# RGB_FPGA_CSI.net
KiCad netlist of a schematic drawn in Altium Designer
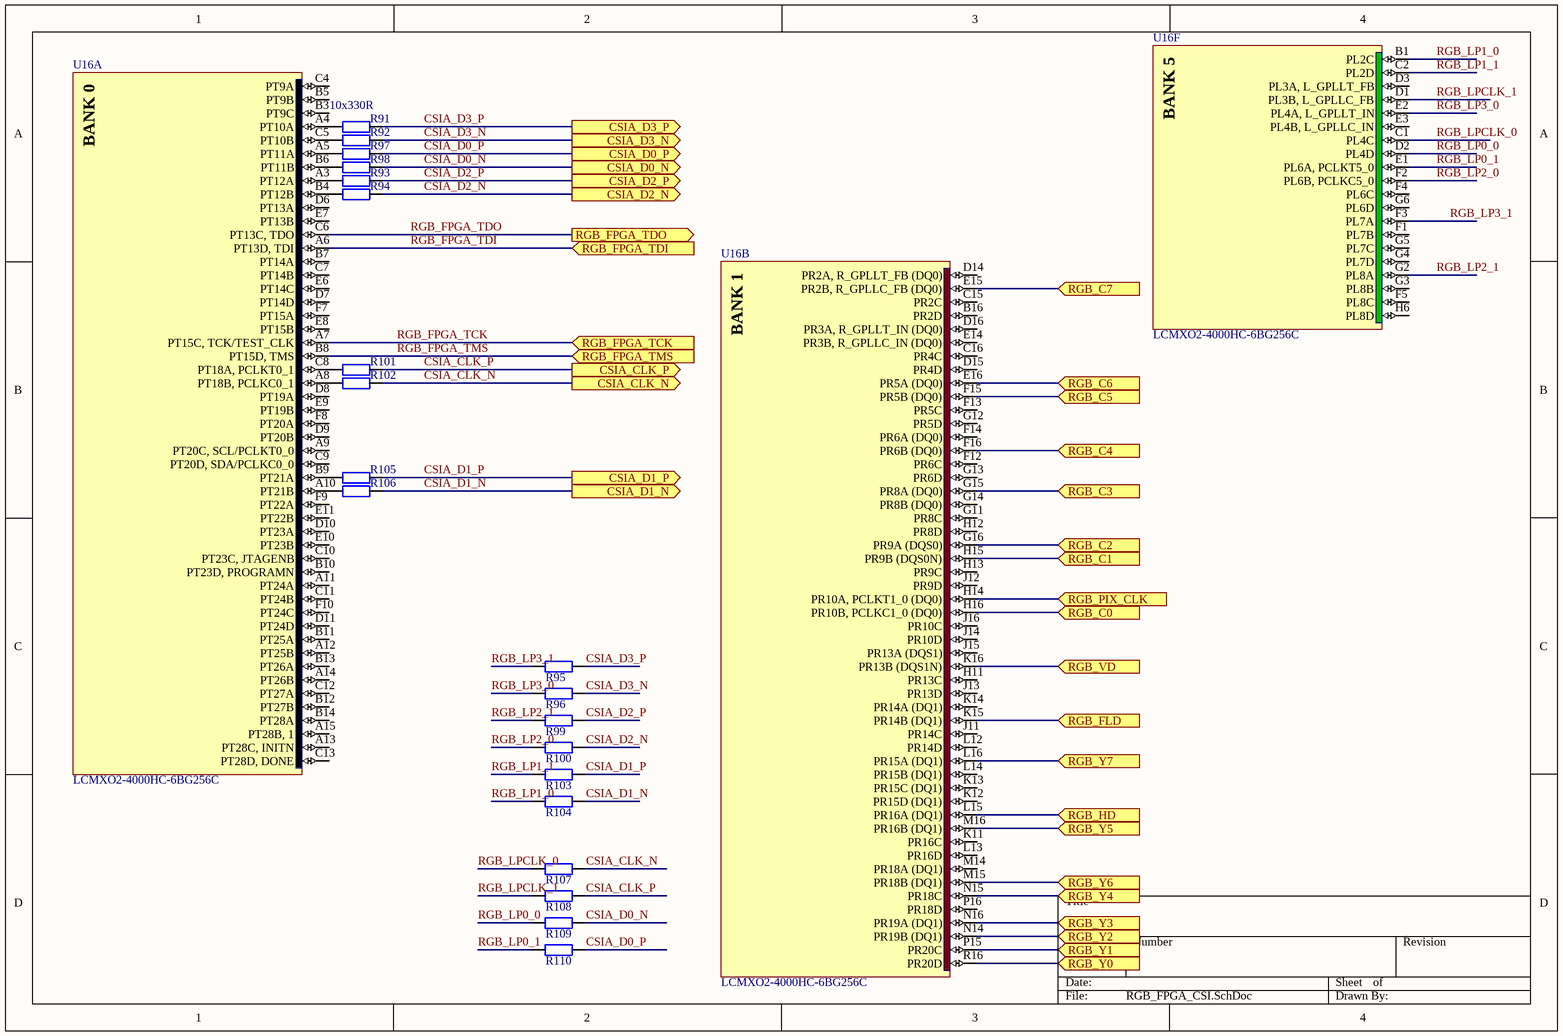
[diagram p0: RGB_FPGA_CSI.SchDoc]

(export (version "E")
  (design (tool "Eeschema 10.0.6"))
  (components
    (comp (ref "R91")
      (value "CRCW0402330RFKED")
      (footprint "0402R_M")
      (description "RES SMD 330 OHM 1% 1/16W 0402")
      (fields (field (name "MANUFACTURER") "Vishay Dale") (field (name "TOLERANCE") "±1%"))
      (libsource (lib "KMTI-main") (part "CRCW0402330RFKED"))
    )
    (comp (ref "R92")
      (value "CRCW0402330RFKED")
      (footprint "0402R_M")
      (description "RES SMD 330 OHM 1% 1/16W 0402")
      (fields (field (name "MANUFACTURER") "Vishay Dale") (field (name "TOLERANCE") "±1%"))
      (libsource (lib "KMTI-main") (part "CRCW0402330RFKED"))
    )
    (comp (ref "R93")
      (value "CRCW0402330RFKED")
      (footprint "0402R_M")
      (description "RES SMD 330 OHM 1% 1/16W 0402")
      (fields (field (name "MANUFACTURER") "Vishay Dale") (field (name "TOLERANCE") "±1%"))
      (libsource (lib "KMTI-main") (part "CRCW0402330RFKED"))
    )
    (comp (ref "R94")
      (value "CRCW0402330RFKED")
      (footprint "0402R_M")
      (description "RES SMD 330 OHM 1% 1/16W 0402")
      (fields (field (name "MANUFACTURER") "Vishay Dale") (field (name "TOLERANCE") "±1%"))
      (libsource (lib "KMTI-main") (part "CRCW0402330RFKED"))
    )
    (comp (ref "R95")
      (value "CRCW040249R9FKED")
      (footprint "0402R_M")
      (description "RES SMD 49.9 OHM 1% 1/16W 0402")
      (fields (field (name "MANUFACTURER") "Vishay Dale") (field (name "TOLERANCE") "±1%"))
      (libsource (lib "KMTI-main") (part "CRCW040249R9FKED"))
    )
    (comp (ref "R96")
      (value "CRCW040249R9FKED")
      (footprint "0402R_M")
      (description "RES SMD 49.9 OHM 1% 1/16W 0402")
      (fields (field (name "MANUFACTURER") "Vishay Dale") (field (name "TOLERANCE") "±1%"))
      (libsource (lib "KMTI-main") (part "CRCW040249R9FKED"))
    )
    (comp (ref "R97")
      (value "CRCW0402330RFKED")
      (footprint "0402R_M")
      (description "RES SMD 330 OHM 1% 1/16W 0402")
      (fields (field (name "MANUFACTURER") "Vishay Dale") (field (name "TOLERANCE") "±1%"))
      (libsource (lib "KMTI-main") (part "CRCW0402330RFKED"))
    )
    (comp (ref "R98")
      (value "CRCW0402330RFKED")
      (footprint "0402R_M")
      (description "RES SMD 330 OHM 1% 1/16W 0402")
      (fields (field (name "MANUFACTURER") "Vishay Dale") (field (name "TOLERANCE") "±1%"))
      (libsource (lib "KMTI-main") (part "CRCW0402330RFKED"))
    )
    (comp (ref "R99")
      (value "CRCW040249R9FKED")
      (footprint "0402R_M")
      (description "RES SMD 49.9 OHM 1% 1/16W 0402")
      (fields (field (name "MANUFACTURER") "Vishay Dale") (field (name "TOLERANCE") "±1%"))
      (libsource (lib "KMTI-main") (part "CRCW040249R9FKED"))
    )
    (comp (ref "R100")
      (value "CRCW040249R9FKED")
      (footprint "0402R_M")
      (description "RES SMD 49.9 OHM 1% 1/16W 0402")
      (fields (field (name "MANUFACTURER") "Vishay Dale") (field (name "TOLERANCE") "±1%"))
      (libsource (lib "KMTI-main") (part "CRCW040249R9FKED"))
    )
    (comp (ref "R101")
      (value "CRCW0402330RFKED")
      (footprint "0402R_M")
      (description "RES SMD 330 OHM 1% 1/16W 0402")
      (fields (field (name "MANUFACTURER") "Vishay Dale") (field (name "TOLERANCE") "±1%"))
      (libsource (lib "KMTI-main") (part "CRCW0402330RFKED"))
    )
    (comp (ref "R102")
      (value "CRCW0402330RFKED")
      (footprint "0402R_M")
      (description "RES SMD 330 OHM 1% 1/16W 0402")
      (fields (field (name "MANUFACTURER") "Vishay Dale") (field (name "TOLERANCE") "±1%"))
      (libsource (lib "KMTI-main") (part "CRCW0402330RFKED"))
    )
    (comp (ref "R103")
      (value "CRCW040249R9FKED")
      (footprint "0402R_M")
      (description "RES SMD 49.9 OHM 1% 1/16W 0402")
      (fields (field (name "MANUFACTURER") "Vishay Dale") (field (name "TOLERANCE") "±1%"))
      (libsource (lib "KMTI-main") (part "CRCW040249R9FKED"))
    )
    (comp (ref "R104")
      (value "CRCW040249R9FKED")
      (footprint "0402R_M")
      (description "RES SMD 49.9 OHM 1% 1/16W 0402")
      (fields (field (name "MANUFACTURER") "Vishay Dale") (field (name "TOLERANCE") "±1%"))
      (libsource (lib "KMTI-main") (part "CRCW040249R9FKED"))
    )
    (comp (ref "R105")
      (value "CRCW0402330RFKED")
      (footprint "0402R_M")
      (description "RES SMD 330 OHM 1% 1/16W 0402")
      (fields (field (name "MANUFACTURER") "Vishay Dale") (field (name "TOLERANCE") "±1%"))
      (libsource (lib "KMTI-main") (part "CRCW0402330RFKED"))
    )
    (comp (ref "R106")
      (value "CRCW0402330RFKED")
      (footprint "0402R_M")
      (description "RES SMD 330 OHM 1% 1/16W 0402")
      (fields (field (name "MANUFACTURER") "Vishay Dale") (field (name "TOLERANCE") "±1%"))
      (libsource (lib "KMTI-main") (part "CRCW0402330RFKED"))
    )
    (comp (ref "R107")
      (value "CRCW040249R9FKED")
      (footprint "0402R_M")
      (description "RES SMD 49.9 OHM 1% 1/16W 0402")
      (fields (field (name "MANUFACTURER") "Vishay Dale") (field (name "TOLERANCE") "±1%"))
      (libsource (lib "") (part "CRCW040249R9FKED_1"))
    )
    (comp (ref "R108")
      (value "CRCW040249R9FKED")
      (footprint "0402R_M")
      (description "RES SMD 49.9 OHM 1% 1/16W 0402")
      (fields (field (name "MANUFACTURER") "Vishay Dale") (field (name "TOLERANCE") "±1%"))
      (libsource (lib "") (part "CRCW040249R9FKED_1"))
    )
    (comp (ref "R109")
      (value "CRCW040249R9FKED")
      (footprint "0402R_M")
      (description "RES SMD 49.9 OHM 1% 1/16W 0402")
      (fields (field (name "MANUFACTURER") "Vishay Dale") (field (name "TOLERANCE") "±1%"))
      (libsource (lib "") (part "CRCW040249R9FKED_1"))
    )
    (comp (ref "R110")
      (value "CRCW040249R9FKED")
      (footprint "0402R_M")
      (description "RES SMD 49.9 OHM 1% 1/16W 0402")
      (fields (field (name "MANUFACTURER") "Vishay Dale") (field (name "TOLERANCE") "±1%"))
      (libsource (lib "") (part "CRCW040249R9FKED_1"))
    )
    (comp (ref "U16")
      (value "LCMXO2-4000HC-6BG256C")
      (footprint "caBGA256")
      (libsource (lib "Altium Content Vault") (part "PLD-LTMXO2-4000-GA256"))
    )
  )
  (nets
    (net (code "1") (name "/CSIA_CLK_N") (class "Default")
      (node (ref "R102") (pin "2") (pinfunction "2_2") (pintype "passive"))
      (node (ref "R107") (pin "2") (pinfunction "2_2") (pintype "passive"))
    )
    (net (code "2") (name "/CSIA_CLK_P") (class "Default")
      (node (ref "R101") (pin "2") (pinfunction "2_2") (pintype "passive"))
      (node (ref "R108") (pin "2") (pinfunction "2_2") (pintype "passive"))
    )
    (net (code "3") (name "/CSIA_D0_N") (class "Default")
      (node (ref "R109") (pin "2") (pinfunction "2_2") (pintype "passive"))
      (node (ref "R98") (pin "2") (pinfunction "2_2") (pintype "passive"))
    )
    (net (code "4") (name "/CSIA_D0_P") (class "Default")
      (node (ref "R110") (pin "2") (pinfunction "2_2") (pintype "passive"))
      (node (ref "R97") (pin "2") (pinfunction "2_2") (pintype "passive"))
    )
    (net (code "5") (name "/CSIA_D1_N") (class "Default")
      (node (ref "R104") (pin "1") (pinfunction "1_1") (pintype "passive"))
      (node (ref "R106") (pin "2") (pinfunction "2_2") (pintype "passive"))
    )
    (net (code "6") (name "/CSIA_D1_P") (class "Default")
      (node (ref "R103") (pin "1") (pinfunction "1_1") (pintype "passive"))
      (node (ref "R105") (pin "2") (pinfunction "2_2") (pintype "passive"))
    )
    (net (code "7") (name "/CSIA_D2_N") (class "Default")
      (node (ref "R100") (pin "1") (pinfunction "1_1") (pintype "passive"))
      (node (ref "R94") (pin "2") (pinfunction "2_2") (pintype "passive"))
    )
    (net (code "8") (name "/CSIA_D2_P") (class "Default")
      (node (ref "R93") (pin "2") (pinfunction "2_2") (pintype "passive"))
      (node (ref "R99") (pin "1") (pinfunction "1_1") (pintype "passive"))
    )
    (net (code "9") (name "/CSIA_D3_N") (class "Default")
      (node (ref "R92") (pin "2") (pinfunction "2_2") (pintype "passive"))
      (node (ref "R96") (pin "1") (pinfunction "1_1") (pintype "passive"))
    )
    (net (code "10") (name "/CSIA_D3_P") (class "Default")
      (node (ref "R91") (pin "2") (pinfunction "2_2") (pintype "passive"))
      (node (ref "R95") (pin "1") (pinfunction "1_1") (pintype "passive"))
    )
    (net (code "11") (name "/RGB_C0") (class "Default")
      (node (ref "U16") (pin "H16") (pinfunction "PR10B,_PCLKC1_0_(DQ0)_H16") (pintype "bidirectional"))
    )
    (net (code "12") (name "/RGB_C1") (class "Default")
      (node (ref "U16") (pin "H15") (pinfunction "PR9B_(DQS0N)_H15") (pintype "bidirectional"))
    )
    (net (code "13") (name "/RGB_C2") (class "Default")
      (node (ref "U16") (pin "G16") (pinfunction "PR9A_(DQS0)_G16") (pintype "bidirectional"))
    )
    (net (code "14") (name "/RGB_C3") (class "Default")
      (node (ref "U16") (pin "G15") (pinfunction "PR8A_(DQ0)_G15") (pintype "bidirectional"))
    )
    (net (code "15") (name "/RGB_C4") (class "Default")
      (node (ref "U16") (pin "F16") (pinfunction "PR6B_(DQ0)_F16") (pintype "bidirectional"))
    )
    (net (code "16") (name "/RGB_C5") (class "Default")
      (node (ref "U16") (pin "F15") (pinfunction "PR5B_(DQ0)_F15") (pintype "bidirectional"))
    )
    (net (code "17") (name "/RGB_C6") (class "Default")
      (node (ref "U16") (pin "E16") (pinfunction "PR5A_(DQ0)_E16") (pintype "bidirectional"))
    )
    (net (code "18") (name "/RGB_C7") (class "Default")
      (node (ref "U16") (pin "E15") (pinfunction "PR2B,_R_GPLLC_FB_(DQ0)_E15") (pintype "bidirectional"))
    )
    (net (code "19") (name "/RGB_FLD") (class "Default")
      (node (ref "U16") (pin "K15") (pinfunction "PR14B_(DQ1)_K15") (pintype "bidirectional"))
    )
    (net (code "20") (name "/RGB_FPGA_TCK") (class "Default")
      (node (ref "U16") (pin "A7") (pinfunction "PT15C,_TCK/TEST_CLK_A7") (pintype "bidirectional"))
    )
    (net (code "21") (name "/RGB_FPGA_TDI") (class "Default")
      (node (ref "U16") (pin "A6") (pinfunction "PT13D,_TDI_A6") (pintype "bidirectional"))
    )
    (net (code "22") (name "/RGB_FPGA_TDO") (class "Default")
      (node (ref "U16") (pin "C6") (pinfunction "PT13C,_TDO_C6") (pintype "bidirectional"))
    )
    (net (code "23") (name "/RGB_FPGA_TMS") (class "Default")
      (node (ref "U16") (pin "B8") (pinfunction "PT15D,_TMS_B8") (pintype "bidirectional"))
    )
    (net (code "24") (name "/RGB_HD") (class "Default")
      (node (ref "U16") (pin "L15") (pinfunction "PR16A_(DQ1)_L15") (pintype "bidirectional"))
    )
    (net (code "25") (name "/RGB_LP0_0") (class "Default")
      (node (ref "R109") (pin "1") (pinfunction "1_1") (pintype "passive"))
      (node (ref "U16") (pin "D2") (pinfunction "PL4D_D2") (pintype "bidirectional"))
    )
    (net (code "26") (name "/RGB_LP0_1") (class "Default")
      (node (ref "R110") (pin "1") (pinfunction "1_1") (pintype "passive"))
      (node (ref "U16") (pin "E1") (pinfunction "PL6A,_PCLKT5_0_E1") (pintype "bidirectional"))
    )
    (net (code "27") (name "/RGB_LP1_0") (class "Default")
      (node (ref "R104") (pin "2") (pinfunction "2_2") (pintype "passive"))
      (node (ref "U16") (pin "B1") (pinfunction "PL2C_B1") (pintype "bidirectional"))
    )
    (net (code "28") (name "/RGB_LP1_1") (class "Default")
      (node (ref "R103") (pin "2") (pinfunction "2_2") (pintype "passive"))
      (node (ref "U16") (pin "C2") (pinfunction "PL2D_C2") (pintype "bidirectional"))
    )
    (net (code "29") (name "/RGB_LP2_0") (class "Default")
      (node (ref "R100") (pin "2") (pinfunction "2_2") (pintype "passive"))
      (node (ref "U16") (pin "F2") (pinfunction "PL6B,_PCLKC5_0_F2") (pintype "bidirectional"))
    )
    (net (code "30") (name "/RGB_LP2_1") (class "Default")
      (node (ref "R99") (pin "2") (pinfunction "2_2") (pintype "passive"))
      (node (ref "U16") (pin "G2") (pinfunction "PL8A_G2") (pintype "bidirectional"))
    )
    (net (code "31") (name "/RGB_LP3_0") (class "Default")
      (node (ref "R96") (pin "2") (pinfunction "2_2") (pintype "passive"))
      (node (ref "U16") (pin "E2") (pinfunction "PL4A,_L_GPLLT_IN_E2") (pintype "bidirectional"))
    )
    (net (code "32") (name "/RGB_LP3_1") (class "Default")
      (node (ref "R95") (pin "2") (pinfunction "2_2") (pintype "passive"))
      (node (ref "U16") (pin "F3") (pinfunction "PL7A_F3") (pintype "bidirectional"))
    )
    (net (code "33") (name "/RGB_LPCLK_0") (class "Default")
      (node (ref "R107") (pin "1") (pinfunction "1_1") (pintype "passive"))
      (node (ref "U16") (pin "C1") (pinfunction "PL4C_C1") (pintype "bidirectional"))
    )
    (net (code "34") (name "/RGB_LPCLK_1") (class "Default")
      (node (ref "R108") (pin "1") (pinfunction "1_1") (pintype "passive"))
      (node (ref "U16") (pin "D1") (pinfunction "PL3B,_L_GPLLC_FB_D1") (pintype "bidirectional"))
    )
    (net (code "35") (name "/RGB_PIX_CLK") (class "Default")
      (node (ref "U16") (pin "H14") (pinfunction "PR10A,_PCLKT1_0_(DQ0)_H14") (pintype "bidirectional"))
    )
    (net (code "36") (name "/RGB_VD") (class "Default")
      (node (ref "U16") (pin "K16") (pinfunction "PR13B_(DQS1N)_K16") (pintype "bidirectional"))
    )
    (net (code "37") (name "/RGB_Y0") (class "Default")
      (node (ref "U16") (pin "R16") (pinfunction "PR20D_R16") (pintype "bidirectional"))
    )
    (net (code "38") (name "/RGB_Y1") (class "Default")
      (node (ref "U16") (pin "P15") (pinfunction "PR20C_P15") (pintype "bidirectional"))
    )
    (net (code "39") (name "/RGB_Y2") (class "Default")
      (node (ref "U16") (pin "N14") (pinfunction "PR19B_(DQ1)_N14") (pintype "bidirectional"))
    )
    (net (code "40") (name "/RGB_Y3") (class "Default")
      (node (ref "U16") (pin "N16") (pinfunction "PR19A_(DQ1)_N16") (pintype "bidirectional"))
    )
    (net (code "41") (name "/RGB_Y4") (class "Default")
      (node (ref "U16") (pin "N15") (pinfunction "PR18C_N15") (pintype "bidirectional"))
    )
    (net (code "42") (name "/RGB_Y5") (class "Default")
      (node (ref "U16") (pin "M16") (pinfunction "PR16B_(DQ1)_M16") (pintype "bidirectional"))
    )
    (net (code "43") (name "/RGB_Y6") (class "Default")
      (node (ref "U16") (pin "M15") (pinfunction "PR18B_(DQ1)_M15") (pintype "bidirectional"))
    )
    (net (code "44") (name "/RGB_Y7") (class "Default")
      (node (ref "U16") (pin "L16") (pinfunction "PR15A_(DQ1)_L16") (pintype "bidirectional"))
    )
    (net (code "45") (name "Net-(U16A-PT10A)") (class "Default")
      (node (ref "R91") (pin "1") (pinfunction "1_1") (pintype "passive"))
      (node (ref "U16") (pin "A4") (pinfunction "PT10A_A4") (pintype "bidirectional"))
    )
    (net (code "46") (name "Net-(U16A-PT10B)") (class "Default")
      (node (ref "R92") (pin "1") (pinfunction "1_1") (pintype "passive"))
      (node (ref "U16") (pin "C5") (pinfunction "PT10B_C5") (pintype "bidirectional"))
    )
    (net (code "47") (name "Net-(U16A-PT11A)") (class "Default")
      (node (ref "R97") (pin "1") (pinfunction "1_1") (pintype "passive"))
      (node (ref "U16") (pin "A5") (pinfunction "PT11A_A5") (pintype "bidirectional"))
    )
    (net (code "48") (name "Net-(U16A-PT11B)") (class "Default")
      (node (ref "R98") (pin "1") (pinfunction "1_1") (pintype "passive"))
      (node (ref "U16") (pin "B6") (pinfunction "PT11B_B6") (pintype "bidirectional"))
    )
    (net (code "49") (name "Net-(U16A-PT12A)") (class "Default")
      (node (ref "R93") (pin "1") (pinfunction "1_1") (pintype "passive"))
      (node (ref "U16") (pin "A3") (pinfunction "PT12A_A3") (pintype "bidirectional"))
    )
    (net (code "50") (name "Net-(U16A-PT12B)") (class "Default")
      (node (ref "R94") (pin "1") (pinfunction "1_1") (pintype "passive"))
      (node (ref "U16") (pin "B4") (pinfunction "PT12B_B4") (pintype "bidirectional"))
    )
    (net (code "51") (name "Net-(U16A-PT18A,_PCLKT0_1)") (class "Default")
      (node (ref "R101") (pin "1") (pinfunction "1_1") (pintype "passive"))
      (node (ref "U16") (pin "C8") (pinfunction "PT18A,_PCLKT0_1_C8") (pintype "bidirectional"))
    )
    (net (code "52") (name "Net-(U16A-PT18B,_PCLKC0_1)") (class "Default")
      (node (ref "R102") (pin "1") (pinfunction "1_1") (pintype "passive"))
      (node (ref "U16") (pin "A8") (pinfunction "PT18B,_PCLKC0_1_A8") (pintype "bidirectional"))
    )
    (net (code "53") (name "Net-(U16A-PT21A)") (class "Default")
      (node (ref "R105") (pin "1") (pinfunction "1_1") (pintype "passive"))
      (node (ref "U16") (pin "B9") (pinfunction "PT21A_B9") (pintype "bidirectional"))
    )
    (net (code "54") (name "Net-(U16A-PT21B)") (class "Default")
      (node (ref "R106") (pin "1") (pinfunction "1_1") (pintype "passive"))
      (node (ref "U16") (pin "A10") (pinfunction "PT21B_A10") (pintype "bidirectional"))
    )
    (net (code "55") (name "unconnected-(U16A-PT9A-PadC4)") (class "Default")
      (node (ref "U16") (pin "C4") (pinfunction "PT9A_C4") (pintype "bidirectional"))
    )
    (net (code "56") (name "unconnected-(U16A-PT9B-PadB5)") (class "Default")
      (node (ref "U16") (pin "B5") (pinfunction "PT9B_B5") (pintype "bidirectional"))
    )
    (net (code "57") (name "unconnected-(U16A-PT9C-PadB3)") (class "Default")
      (node (ref "U16") (pin "B3") (pinfunction "PT9C_B3") (pintype "bidirectional"))
    )
    (net (code "58") (name "unconnected-(U16A-PT13A-PadD6)") (class "Default")
      (node (ref "U16") (pin "D6") (pinfunction "PT13A_D6") (pintype "bidirectional"))
    )
    (net (code "59") (name "unconnected-(U16A-PT13B-PadE7)") (class "Default")
      (node (ref "U16") (pin "E7") (pinfunction "PT13B_E7") (pintype "bidirectional"))
    )
    (net (code "60") (name "unconnected-(U16A-PT14A-PadB7)") (class "Default")
      (node (ref "U16") (pin "B7") (pinfunction "PT14A_B7") (pintype "bidirectional"))
    )
    (net (code "61") (name "unconnected-(U16A-PT14B-PadC7)") (class "Default")
      (node (ref "U16") (pin "C7") (pinfunction "PT14B_C7") (pintype "bidirectional"))
    )
    (net (code "62") (name "unconnected-(U16A-PT14C-PadE6)") (class "Default")
      (node (ref "U16") (pin "E6") (pinfunction "PT14C_E6") (pintype "bidirectional"))
    )
    (net (code "63") (name "unconnected-(U16A-PT14D-PadD7)") (class "Default")
      (node (ref "U16") (pin "D7") (pinfunction "PT14D_D7") (pintype "bidirectional"))
    )
    (net (code "64") (name "unconnected-(U16A-PT15A-PadF7)") (class "Default")
      (node (ref "U16") (pin "F7") (pinfunction "PT15A_F7") (pintype "bidirectional"))
    )
    (net (code "65") (name "unconnected-(U16A-PT15B-PadE8)") (class "Default")
      (node (ref "U16") (pin "E8") (pinfunction "PT15B_E8") (pintype "bidirectional"))
    )
    (net (code "66") (name "unconnected-(U16A-PT19A-PadD8)") (class "Default")
      (node (ref "U16") (pin "D8") (pinfunction "PT19A_D8") (pintype "bidirectional"))
    )
    (net (code "67") (name "unconnected-(U16A-PT19B-PadE9)") (class "Default")
      (node (ref "U16") (pin "E9") (pinfunction "PT19B_E9") (pintype "bidirectional"))
    )
    (net (code "68") (name "unconnected-(U16A-PT20A-PadF8)") (class "Default")
      (node (ref "U16") (pin "F8") (pinfunction "PT20A_F8") (pintype "bidirectional"))
    )
    (net (code "69") (name "unconnected-(U16A-PT20B-PadD9)") (class "Default")
      (node (ref "U16") (pin "D9") (pinfunction "PT20B_D9") (pintype "bidirectional"))
    )
    (net (code "70") (name "unconnected-(U16A-PT20C,_SCL{slash}PCLKT0_0-PadA9)") (class "Default")
      (node (ref "U16") (pin "A9") (pinfunction "PT20C,_SCL/PCLKT0_0_A9") (pintype "bidirectional"))
    )
    (net (code "71") (name "unconnected-(U16A-PT20D,_SDA{slash}PCLKC0_0-PadC9)") (class "Default")
      (node (ref "U16") (pin "C9") (pinfunction "PT20D,_SDA/PCLKC0_0_C9") (pintype "bidirectional"))
    )
    (net (code "72") (name "unconnected-(U16A-PT22A-PadF9)") (class "Default")
      (node (ref "U16") (pin "F9") (pinfunction "PT22A_F9") (pintype "bidirectional"))
    )
    (net (code "73") (name "unconnected-(U16A-PT22B-PadE11)") (class "Default")
      (node (ref "U16") (pin "E11") (pinfunction "PT22B_E11") (pintype "bidirectional"))
    )
    (net (code "74") (name "unconnected-(U16A-PT23A-PadD10)") (class "Default")
      (node (ref "U16") (pin "D10") (pinfunction "PT23A_D10") (pintype "bidirectional"))
    )
    (net (code "75") (name "unconnected-(U16A-PT23B-PadE10)") (class "Default")
      (node (ref "U16") (pin "E10") (pinfunction "PT23B_E10") (pintype "bidirectional"))
    )
    (net (code "76") (name "unconnected-(U16A-PT23C,_JTAGENB-PadC10)") (class "Default")
      (node (ref "U16") (pin "C10") (pinfunction "PT23C,_JTAGENB_C10") (pintype "bidirectional"))
    )
    (net (code "77") (name "unconnected-(U16A-PT23D,_PROGRAMN-PadB10)") (class "Default")
      (node (ref "U16") (pin "B10") (pinfunction "PT23D,_PROGRAMN_B10") (pintype "bidirectional"))
    )
    (net (code "78") (name "unconnected-(U16A-PT24A-PadA11)") (class "Default")
      (node (ref "U16") (pin "A11") (pinfunction "PT24A_A11") (pintype "bidirectional"))
    )
    (net (code "79") (name "unconnected-(U16A-PT24B-PadC11)") (class "Default")
      (node (ref "U16") (pin "C11") (pinfunction "PT24B_C11") (pintype "bidirectional"))
    )
    (net (code "80") (name "unconnected-(U16A-PT24C-PadF10)") (class "Default")
      (node (ref "U16") (pin "F10") (pinfunction "PT24C_F10") (pintype "bidirectional"))
    )
    (net (code "81") (name "unconnected-(U16A-PT24D-PadD11)") (class "Default")
      (node (ref "U16") (pin "D11") (pinfunction "PT24D_D11") (pintype "bidirectional"))
    )
    (net (code "82") (name "unconnected-(U16A-PT25A-PadB11)") (class "Default")
      (node (ref "U16") (pin "B11") (pinfunction "PT25A_B11") (pintype "bidirectional"))
    )
    (net (code "83") (name "unconnected-(U16A-PT25B-PadA12)") (class "Default")
      (node (ref "U16") (pin "A12") (pinfunction "PT25B_A12") (pintype "bidirectional"))
    )
    (net (code "84") (name "unconnected-(U16A-PT26A-PadB13)") (class "Default")
      (node (ref "U16") (pin "B13") (pinfunction "PT26A_B13") (pintype "bidirectional"))
    )
    (net (code "85") (name "unconnected-(U16A-PT26B-PadA14)") (class "Default")
      (node (ref "U16") (pin "A14") (pinfunction "PT26B_A14") (pintype "bidirectional"))
    )
    (net (code "86") (name "unconnected-(U16A-PT27A-PadC12)") (class "Default")
      (node (ref "U16") (pin "C12") (pinfunction "PT27A_C12") (pintype "bidirectional"))
    )
    (net (code "87") (name "unconnected-(U16A-PT27B-PadB12)") (class "Default")
      (node (ref "U16") (pin "B12") (pinfunction "PT27B_B12") (pintype "bidirectional"))
    )
    (net (code "88") (name "unconnected-(U16A-PT28A-PadB14)") (class "Default")
      (node (ref "U16") (pin "B14") (pinfunction "PT28A_B14") (pintype "bidirectional"))
    )
    (net (code "89") (name "unconnected-(U16A-PT28B,_1-PadA15)") (class "Default")
      (node (ref "U16") (pin "A15") (pinfunction "PT28B,_1_A15") (pintype "bidirectional"))
    )
    (net (code "90") (name "unconnected-(U16A-PT28C,_INITN-PadA13)") (class "Default")
      (node (ref "U16") (pin "A13") (pinfunction "PT28C,_INITN_A13") (pintype "bidirectional"))
    )
    (net (code "91") (name "unconnected-(U16A-PT28D,_DONE-PadC13)") (class "Default")
      (node (ref "U16") (pin "C13") (pinfunction "PT28D,_DONE_C13") (pintype "bidirectional"))
    )
    (net (code "92") (name "unconnected-(U16B-PR2A,_R_GPLLT_FB_(DQ0)-PadD14)") (class "Default")
      (node (ref "U16") (pin "D14") (pinfunction "PR2A,_R_GPLLT_FB_(DQ0)_D14") (pintype "bidirectional"))
    )
    (net (code "93") (name "unconnected-(U16B-PR2C-PadC15)") (class "Default")
      (node (ref "U16") (pin "C15") (pinfunction "PR2C_C15") (pintype "bidirectional"))
    )
    (net (code "94") (name "unconnected-(U16B-PR2D-PadB16)") (class "Default")
      (node (ref "U16") (pin "B16") (pinfunction "PR2D_B16") (pintype "bidirectional"))
    )
    (net (code "95") (name "unconnected-(U16B-PR3A,_R_GPLLT_IN_(DQ0)-PadD16)") (class "Default")
      (node (ref "U16") (pin "D16") (pinfunction "PR3A,_R_GPLLT_IN_(DQ0)_D16") (pintype "bidirectional"))
    )
    (net (code "96") (name "unconnected-(U16B-PR3B,_R_GPLLC_IN_(DQ0)-PadE14)") (class "Default")
      (node (ref "U16") (pin "E14") (pinfunction "PR3B,_R_GPLLC_IN_(DQ0)_E14") (pintype "bidirectional"))
    )
    (net (code "97") (name "unconnected-(U16B-PR4C-PadC16)") (class "Default")
      (node (ref "U16") (pin "C16") (pinfunction "PR4C_C16") (pintype "bidirectional"))
    )
    (net (code "98") (name "unconnected-(U16B-PR4D-PadD15)") (class "Default")
      (node (ref "U16") (pin "D15") (pinfunction "PR4D_D15") (pintype "bidirectional"))
    )
    (net (code "99") (name "unconnected-(U16B-PR5C-PadF13)") (class "Default")
      (node (ref "U16") (pin "F13") (pinfunction "PR5C_F13") (pintype "bidirectional"))
    )
    (net (code "100") (name "unconnected-(U16B-PR5D-PadG12)") (class "Default")
      (node (ref "U16") (pin "G12") (pinfunction "PR5D_G12") (pintype "bidirectional"))
    )
    (net (code "101") (name "unconnected-(U16B-PR6A_(DQ0)-PadF14)") (class "Default")
      (node (ref "U16") (pin "F14") (pinfunction "PR6A_(DQ0)_F14") (pintype "bidirectional"))
    )
    (net (code "102") (name "unconnected-(U16B-PR6C-PadF12)") (class "Default")
      (node (ref "U16") (pin "F12") (pinfunction "PR6C_F12") (pintype "bidirectional"))
    )
    (net (code "103") (name "unconnected-(U16B-PR6D-PadG13)") (class "Default")
      (node (ref "U16") (pin "G13") (pinfunction "PR6D_G13") (pintype "bidirectional"))
    )
    (net (code "104") (name "unconnected-(U16B-PR8B_(DQ0)-PadG14)") (class "Default")
      (node (ref "U16") (pin "G14") (pinfunction "PR8B_(DQ0)_G14") (pintype "bidirectional"))
    )
    (net (code "105") (name "unconnected-(U16B-PR8C-PadG11)") (class "Default")
      (node (ref "U16") (pin "G11") (pinfunction "PR8C_G11") (pintype "bidirectional"))
    )
    (net (code "106") (name "unconnected-(U16B-PR8D-PadH12)") (class "Default")
      (node (ref "U16") (pin "H12") (pinfunction "PR8D_H12") (pintype "bidirectional"))
    )
    (net (code "107") (name "unconnected-(U16B-PR9C-PadH13)") (class "Default")
      (node (ref "U16") (pin "H13") (pinfunction "PR9C_H13") (pintype "bidirectional"))
    )
    (net (code "108") (name "unconnected-(U16B-PR9D-PadJ12)") (class "Default")
      (node (ref "U16") (pin "J12") (pinfunction "PR9D_J12") (pintype "bidirectional"))
    )
    (net (code "109") (name "unconnected-(U16B-PR10C-PadJ16)") (class "Default")
      (node (ref "U16") (pin "J16") (pinfunction "PR10C_J16") (pintype "bidirectional"))
    )
    (net (code "110") (name "unconnected-(U16B-PR10D-PadJ14)") (class "Default")
      (node (ref "U16") (pin "J14") (pinfunction "PR10D_J14") (pintype "bidirectional"))
    )
    (net (code "111") (name "unconnected-(U16B-PR13A_(DQS1)-PadJ15)") (class "Default")
      (node (ref "U16") (pin "J15") (pinfunction "PR13A_(DQS1)_J15") (pintype "bidirectional"))
    )
    (net (code "112") (name "unconnected-(U16B-PR13C-PadH11)") (class "Default")
      (node (ref "U16") (pin "H11") (pinfunction "PR13C_H11") (pintype "bidirectional"))
    )
    (net (code "113") (name "unconnected-(U16B-PR13D-PadJ13)") (class "Default")
      (node (ref "U16") (pin "J13") (pinfunction "PR13D_J13") (pintype "bidirectional"))
    )
    (net (code "114") (name "unconnected-(U16B-PR14A_(DQ1)-PadK14)") (class "Default")
      (node (ref "U16") (pin "K14") (pinfunction "PR14A_(DQ1)_K14") (pintype "bidirectional"))
    )
    (net (code "115") (name "unconnected-(U16B-PR14C-PadJ11)") (class "Default")
      (node (ref "U16") (pin "J11") (pinfunction "PR14C_J11") (pintype "bidirectional"))
    )
    (net (code "116") (name "unconnected-(U16B-PR14D-PadL12)") (class "Default")
      (node (ref "U16") (pin "L12") (pinfunction "PR14D_L12") (pintype "bidirectional"))
    )
    (net (code "117") (name "unconnected-(U16B-PR15B_(DQ1)-PadL14)") (class "Default")
      (node (ref "U16") (pin "L14") (pinfunction "PR15B_(DQ1)_L14") (pintype "bidirectional"))
    )
    (net (code "118") (name "unconnected-(U16B-PR15C_(DQ1)-PadK13)") (class "Default")
      (node (ref "U16") (pin "K13") (pinfunction "PR15C_(DQ1)_K13") (pintype "bidirectional"))
    )
    (net (code "119") (name "unconnected-(U16B-PR15D_(DQ1)-PadK12)") (class "Default")
      (node (ref "U16") (pin "K12") (pinfunction "PR15D_(DQ1)_K12") (pintype "bidirectional"))
    )
    (net (code "120") (name "unconnected-(U16B-PR16C-PadK11)") (class "Default")
      (node (ref "U16") (pin "K11") (pinfunction "PR16C_K11") (pintype "bidirectional"))
    )
    (net (code "121") (name "unconnected-(U16B-PR16D-PadL13)") (class "Default")
      (node (ref "U16") (pin "L13") (pinfunction "PR16D_L13") (pintype "bidirectional"))
    )
    (net (code "122") (name "unconnected-(U16B-PR18A_(DQ1)-PadM14)") (class "Default")
      (node (ref "U16") (pin "M14") (pinfunction "PR18A_(DQ1)_M14") (pintype "bidirectional"))
    )
    (net (code "123") (name "unconnected-(U16B-PR18D-PadP16)") (class "Default")
      (node (ref "U16") (pin "P16") (pinfunction "PR18D_P16") (pintype "bidirectional"))
    )
    (net (code "124") (name "unconnected-(U16F-PL3A,_L_GPLLT_FB-PadD3)") (class "Default")
      (node (ref "U16") (pin "D3") (pinfunction "PL3A,_L_GPLLT_FB_D3") (pintype "bidirectional"))
    )
    (net (code "125") (name "unconnected-(U16F-PL4B,_L_GPLLC_IN-PadE3)") (class "Default")
      (node (ref "U16") (pin "E3") (pinfunction "PL4B,_L_GPLLC_IN_E3") (pintype "bidirectional"))
    )
    (net (code "126") (name "unconnected-(U16F-PL6C-PadF4)") (class "Default")
      (node (ref "U16") (pin "F4") (pinfunction "PL6C_F4") (pintype "bidirectional"))
    )
    (net (code "127") (name "unconnected-(U16F-PL6D-PadG6)") (class "Default")
      (node (ref "U16") (pin "G6") (pinfunction "PL6D_G6") (pintype "bidirectional"))
    )
    (net (code "128") (name "unconnected-(U16F-PL7B-PadF1)") (class "Default")
      (node (ref "U16") (pin "F1") (pinfunction "PL7B_F1") (pintype "bidirectional"))
    )
    (net (code "129") (name "unconnected-(U16F-PL7C-PadG5)") (class "Default")
      (node (ref "U16") (pin "G5") (pinfunction "PL7C_G5") (pintype "bidirectional"))
    )
    (net (code "130") (name "unconnected-(U16F-PL7D-PadG4)") (class "Default")
      (node (ref "U16") (pin "G4") (pinfunction "PL7D_G4") (pintype "bidirectional"))
    )
    (net (code "131") (name "unconnected-(U16F-PL8B-PadG3)") (class "Default")
      (node (ref "U16") (pin "G3") (pinfunction "PL8B_G3") (pintype "bidirectional"))
    )
    (net (code "132") (name "unconnected-(U16F-PL8C-PadF5)") (class "Default")
      (node (ref "U16") (pin "F5") (pinfunction "PL8C_F5") (pintype "bidirectional"))
    )
    (net (code "133") (name "unconnected-(U16F-PL8D-PadH6)") (class "Default")
      (node (ref "U16") (pin "H6") (pinfunction "PL8D_H6") (pintype "bidirectional"))
    )
  )
)
